# AQ_sensor_SIGFOX.net
KiCad netlist of a schematic drawn in EAGLE
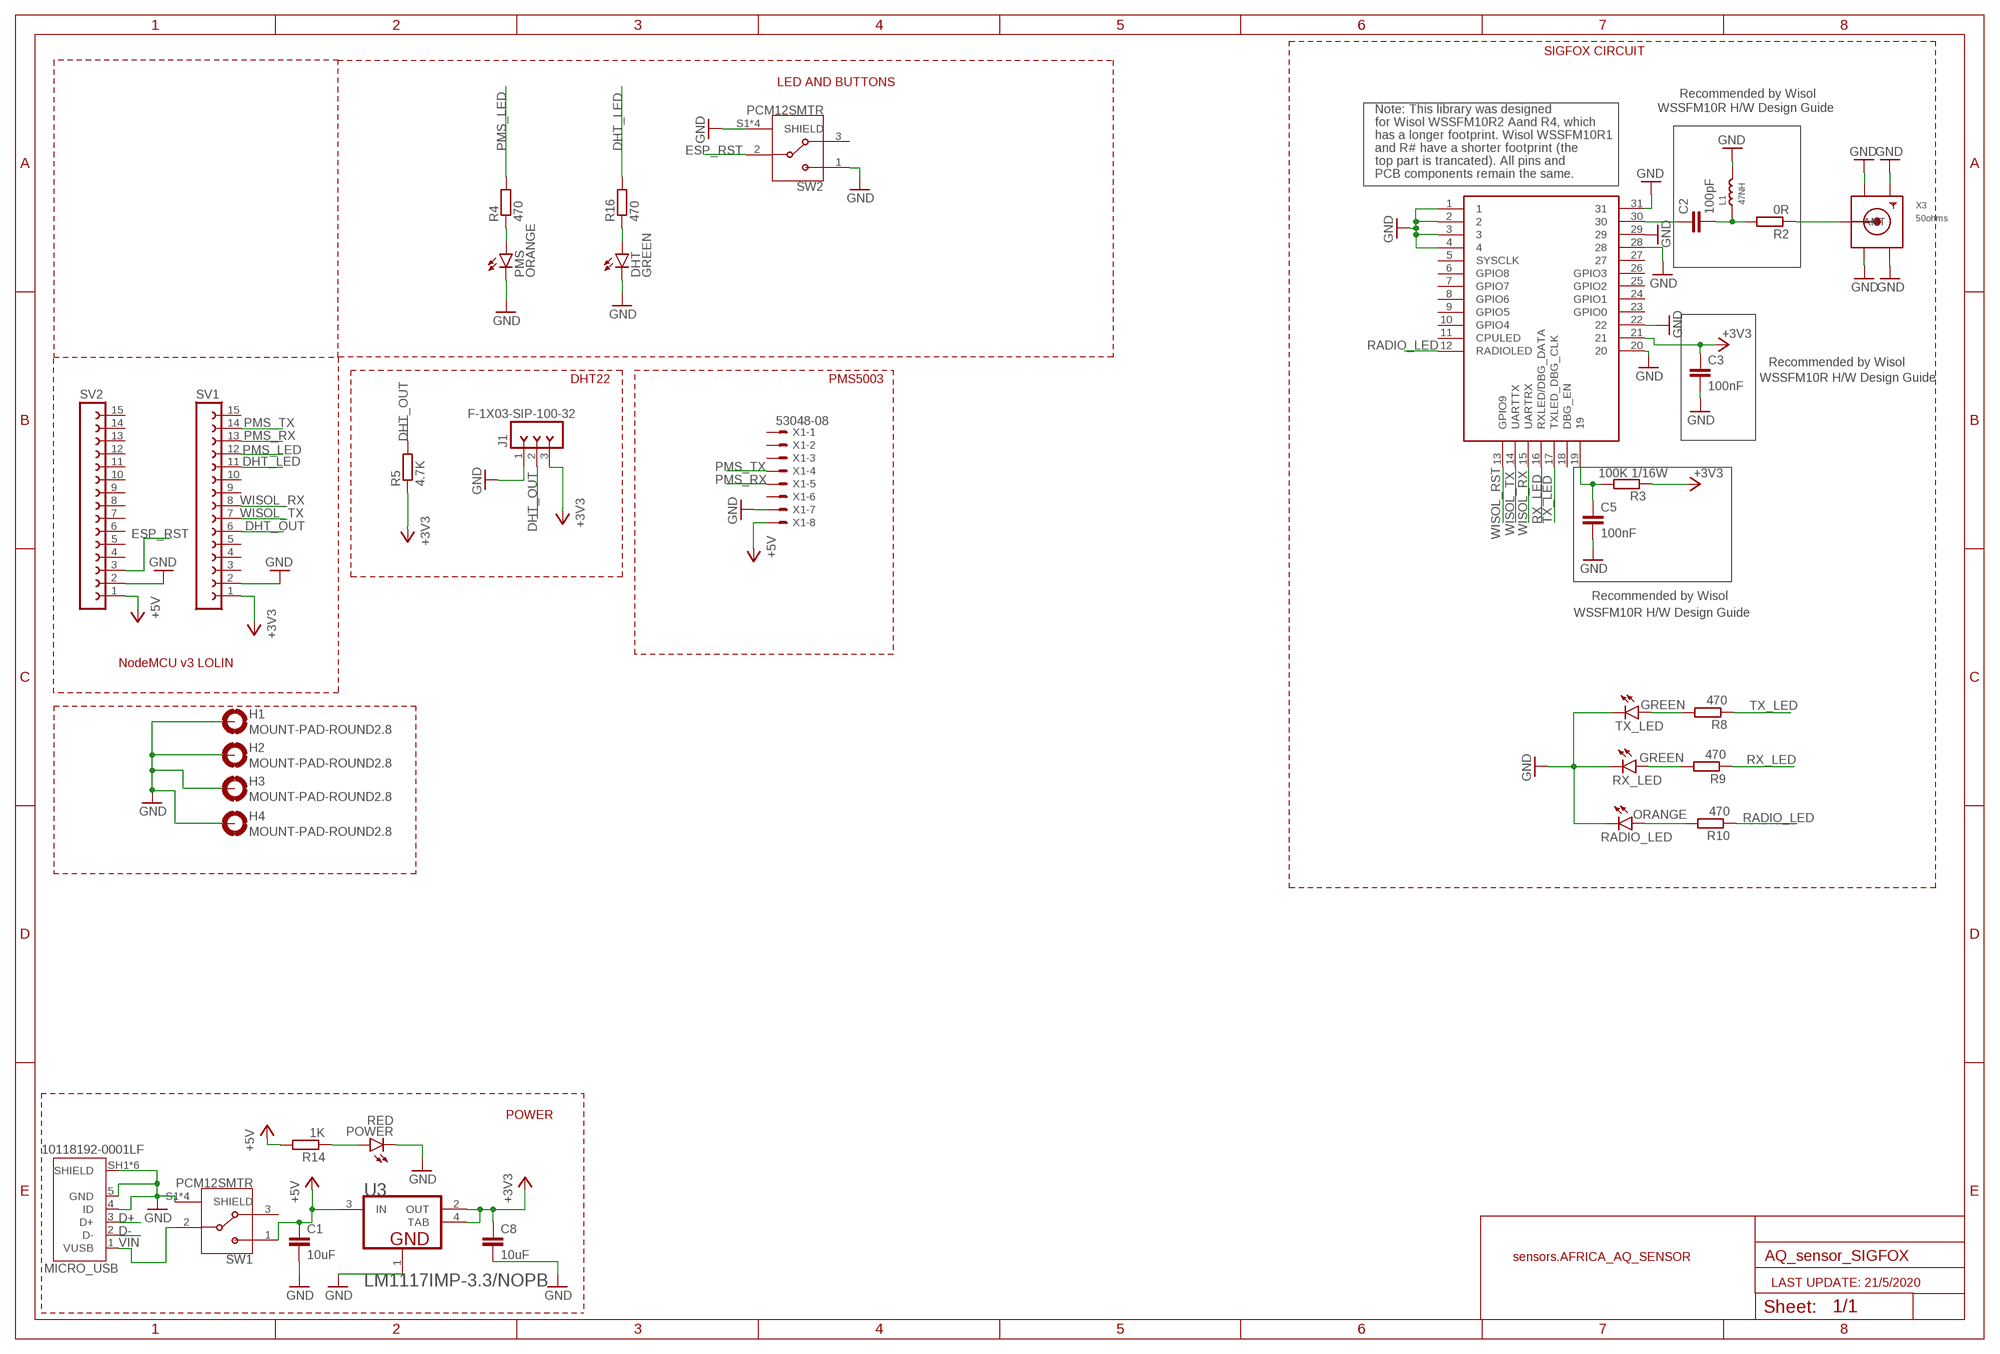
[diagram p0: schematic, sheet 1]

(export (version "E")
  (design (tool "Eeschema 10.0.6"))
  (components
    (comp (ref "C1")
      (value "10uF")
      (footprint "eagle-import:C0603")
      (libsource (lib "eagle-import") (part "C-EUC0603"))
    )
    (comp (ref "C2")
      (value "100pF")
      (footprint "eagle-import:C0603")
      (libsource (lib "eagle-import") (part "C-EUC0603"))
    )
    (comp (ref "C3")
      (value "100nF")
      (footprint "eagle-import:C0603")
      (libsource (lib "eagle-import") (part "C-EUC0603"))
    )
    (comp (ref "C5")
      (value "100nF")
      (footprint "eagle-import:C0603")
      (libsource (lib "eagle-import") (part "C-EUC0603"))
    )
    (comp (ref "C8")
      (value "10uF")
      (footprint "eagle-import:C0603")
      (libsource (lib "eagle-import") (part "C-EUC0603"))
    )
    (comp (ref "DHT")
      (value "GREEN")
      (footprint "eagle-import:CHIP-LED0603")
      (libsource (lib "eagle-import") (part "LEDCHIP-LED0603"))
    )
    (comp (ref "H1")
      (value "MOUNT-PAD-ROUND2.8")
      (footprint "eagle-import:2,8-PAD")
      (libsource (lib "eagle-import") (part "MOUNT-PAD-ROUND2.8"))
    )
    (comp (ref "H2")
      (value "MOUNT-PAD-ROUND2.8")
      (footprint "eagle-import:2,8-PAD")
      (libsource (lib "eagle-import") (part "MOUNT-PAD-ROUND2.8"))
    )
    (comp (ref "H3")
      (value "MOUNT-PAD-ROUND2.8")
      (footprint "eagle-import:2,8-PAD")
      (libsource (lib "eagle-import") (part "MOUNT-PAD-ROUND2.8"))
    )
    (comp (ref "H4")
      (value "MOUNT-PAD-ROUND2.8")
      (footprint "eagle-import:2,8-PAD")
      (libsource (lib "eagle-import") (part "MOUNT-PAD-ROUND2.8"))
    )
    (comp (ref "J1")
      (value "F-1X03-SIP-100-32")
      (footprint "eagle-import:SIP-100-03-32")
      (libsource (lib "eagle-import") (part "F-1X03-SIP-100-32"))
    )
    (comp (ref "L1")
      (value "47NH")
      (footprint "eagle-import:L0805")
      (fields (field (name "MPN") "LQM2MPN2R2MG0"))
      (libsource (lib "eagle-import") (part "SMD-INDUCTOR-2.2UH-20%-1.2A(0805)"))
    )
    (comp (ref "MICRO_USB")
      (value "10118192-0001LF")
      (footprint "eagle-import:AMPHENOL_10118192-0001LF")
      (fields (field (name "MF") "Amphenol ICC"))
      (libsource (lib "eagle-import") (part "10118192-0001LF"))
    )
    (comp (ref "PMS")
      (value "ORANGE")
      (footprint "eagle-import:CHIP-LED0603")
      (libsource (lib "eagle-import") (part "LEDCHIP-LED0603"))
    )
    (comp (ref "POWER")
      (value "RED")
      (footprint "eagle-import:CHIP-LED0603")
      (libsource (lib "eagle-import") (part "LEDCHIP-LED0603"))
    )
    (comp (ref "R2")
      (value "0R")
      (footprint "eagle-import:R0603")
      (libsource (lib "eagle-import") (part "R-EU_R0603"))
    )
    (comp (ref "R3")
      (value "100K 1/16W")
      (footprint "eagle-import:R0603")
      (libsource (lib "eagle-import") (part "R-EU_R0603"))
    )
    (comp (ref "R4")
      (value "470")
      (footprint "eagle-import:R0603")
      (libsource (lib "eagle-import") (part "R-EU_R0603"))
    )
    (comp (ref "R5")
      (value "4.7K")
      (footprint "eagle-import:R0603")
      (libsource (lib "eagle-import") (part "R-EU_R0603"))
    )
    (comp (ref "R8")
      (value "470")
      (footprint "eagle-import:R0603")
      (libsource (lib "eagle-import") (part "R-EU_R0603"))
    )
    (comp (ref "R9")
      (value "470")
      (footprint "eagle-import:R0603")
      (libsource (lib "eagle-import") (part "R-EU_R0603"))
    )
    (comp (ref "R10")
      (value "470")
      (footprint "eagle-import:R0603")
      (libsource (lib "eagle-import") (part "R-EU_R0603"))
    )
    (comp (ref "R14")
      (value "1K")
      (footprint "eagle-import:R0603")
      (libsource (lib "eagle-import") (part "R-EU_R0603"))
    )
    (comp (ref "R16")
      (value "470")
      (footprint "eagle-import:R0603")
      (libsource (lib "eagle-import") (part "R-EU_R0603"))
    )
    (comp (ref "RADIO_LED")
      (value "ORANGE")
      (footprint "eagle-import:CHIP-LED0603")
      (libsource (lib "eagle-import") (part "LEDCHIP-LED0603"))
    )
    (comp (ref "RX_LED")
      (value "GREEN")
      (footprint "eagle-import:CHIP-LED0603")
      (libsource (lib "eagle-import") (part "LEDCHIP-LED0603"))
    )
    (comp (ref "SV1")
      (value "FE15-1")
      (footprint "eagle-import:FE15")
      (libsource (lib "eagle-import") (part "FE15-1"))
    )
    (comp (ref "SV2")
      (value "FE15-1")
      (footprint "eagle-import:FE15")
      (libsource (lib "eagle-import") (part "FE15-1"))
    )
    (comp (ref "SW1")
      (value "PCM12SMTR")
      (footprint "eagle-import:SW_PCM12SMTR")
      (fields (field (name "MF") "C&K"))
      (libsource (lib "eagle-import") (part "PCM12SMTR"))
    )
    (comp (ref "SW2")
      (value "PCM12SMTR")
      (footprint "eagle-import:SW_PCM12SMTR")
      (fields (field (name "MF") "C&K"))
      (libsource (lib "eagle-import") (part "PCM12SMTR"))
    )
    (comp (ref "TX_LED")
      (value "GREEN")
      (footprint "eagle-import:CHIP-LED0603")
      (libsource (lib "eagle-import") (part "LEDCHIP-LED0603"))
    )
    (comp (ref "U$1")
      (value "WSSFM10RWSSFM10R2R4")
      (footprint "eagle-import:WSSFM10R")
      (libsource (lib "eagle-import") (part "WSSFM10RWSSFM10R2R4"))
    )
    (comp (ref "U3")
      (value "TEXAS_INSTRUMENTS_LM1117IMP-3.3-NOPBTEXAS_INSTRUMENTS_LM1117IMP-3.3-NOPB_0_0")
      (footprint "eagle-import:TEXAS_INSTRUMENTS_LM1117IMP-3.3-NOPB_0")
      (fields (field (name "MF") "Texas Instruments") (field (name "MPN") "LM1117IMP-3.3/NOPB"))
      (libsource (lib "eagle-import") (part "TEXAS_INSTRUMENTS_LM1117IMP-3.3-NOPBTEXAS_INSTRUMENTS_LM1117IMP-3.3-NOPB_0_0"))
    )
    (comp (ref "X1")
      (value "53048-08")
      (footprint "eagle-import:53048-08")
      (fields (field (name "MF") "WALDOM/MOLEX") (field (name "MPN") "53048-0810"))
      (libsource (lib "eagle-import") (part "53?-08048"))
    )
    (comp (ref "X3")
      (value "50ohms")
      (footprint "eagle-import:SMA_EDGELAUNCH_UFL")
      (libsource (lib "eagle-import") (part "SMACONNECTOR_EDGE_UFL"))
    )
  )
  (nets
    (net (code "1") (name "+3V3") (class "Default")
      (node (ref "C3") (pin "1") (pinfunction "1_1") (pintype "passive"))
      (node (ref "C8") (pin "1") (pinfunction "1_1") (pintype "passive"))
      (node (ref "J1") (pin "3") (pinfunction "3_3") (pintype "passive"))
      (node (ref "R3") (pin "1") (pinfunction "1_1") (pintype "passive"))
      (node (ref "R5") (pin "1") (pinfunction "1_1") (pintype "passive"))
      (node (ref "SV1") (pin "1") (pinfunction "1_1") (pintype "passive"))
      (node (ref "U$1") (pin "21") (pinfunction "21_21") (pintype "bidirectional"))
      (node (ref "U3") (pin "2") (pinfunction "OUT_2") (pintype "power_in"))
      (node (ref "U3") (pin "4") (pinfunction "TAB_4") (pintype "power_in"))
    )
    (net (code "2") (name "+5V") (class "Default")
      (node (ref "C1") (pin "1") (pinfunction "1_1") (pintype "passive"))
      (node (ref "R14") (pin "2") (pinfunction "2_2") (pintype "passive"))
      (node (ref "SV2") (pin "1") (pinfunction "1_1") (pintype "passive"))
      (node (ref "SW1") (pin "1") (pinfunction "1_1") (pintype "passive"))
      (node (ref "U3") (pin "3") (pinfunction "IN_3") (pintype "power_in"))
      (node (ref "X1") (pin "8") (pinfunction "S_8") (pintype "passive"))
    )
    (net (code "3") (name "/D+") (class "Default")
      (node (ref "MICRO_USB") (pin "3") (pinfunction "D+_3") (pintype "passive"))
    )
    (net (code "4") (name "/D-") (class "Default")
      (node (ref "MICRO_USB") (pin "2") (pinfunction "D-_2") (pintype "passive"))
    )
    (net (code "5") (name "/DHT_LED") (class "Default")
      (node (ref "R16") (pin "2") (pinfunction "2_2") (pintype "passive"))
      (node (ref "SV1") (pin "11") (pinfunction "11_11") (pintype "passive"))
    )
    (net (code "6") (name "/DHT_OUT") (class "Default")
      (node (ref "J1") (pin "2") (pinfunction "2_2") (pintype "passive"))
      (node (ref "R5") (pin "2") (pinfunction "2_2") (pintype "passive"))
      (node (ref "SV1") (pin "6") (pinfunction "6_6") (pintype "passive"))
    )
    (net (code "7") (name "/ESP_RST") (class "Default")
      (node (ref "SV2") (pin "3") (pinfunction "3_3") (pintype "passive"))
      (node (ref "SW2") (pin "2") (pinfunction "2_2") (pintype "passive"))
    )
    (net (code "8") (name "/PMS_LED") (class "Default")
      (node (ref "R4") (pin "2") (pinfunction "2_2") (pintype "passive"))
      (node (ref "SV1") (pin "12") (pinfunction "12_12") (pintype "passive"))
    )
    (net (code "9") (name "/PMS_RX") (class "Default")
      (node (ref "SV1") (pin "13") (pinfunction "13_13") (pintype "passive"))
      (node (ref "X1") (pin "5") (pinfunction "S_5") (pintype "passive"))
    )
    (net (code "10") (name "/PMS_TX") (class "Default")
      (node (ref "SV1") (pin "14") (pinfunction "14_14") (pintype "passive"))
      (node (ref "X1") (pin "4") (pinfunction "S_4") (pintype "passive"))
    )
    (net (code "11") (name "/RADIO_LED") (class "Default")
      (node (ref "R10") (pin "1") (pinfunction "1_1") (pintype "passive"))
      (node (ref "U$1") (pin "12") (pinfunction "RADIOLED_12") (pintype "bidirectional"))
    )
    (net (code "12") (name "/RX_LED") (class "Default")
      (node (ref "R9") (pin "1") (pinfunction "1_1") (pintype "passive"))
      (node (ref "U$1") (pin "16") (pinfunction "RXLED/DBG_DATA_16") (pintype "bidirectional"))
    )
    (net (code "13") (name "/TX_LED") (class "Default")
      (node (ref "R8") (pin "1") (pinfunction "1_1") (pintype "passive"))
      (node (ref "U$1") (pin "17") (pinfunction "TXLED_DBG_CLK_17") (pintype "bidirectional"))
    )
    (net (code "14") (name "/VIN") (class "Default")
      (node (ref "MICRO_USB") (pin "1") (pinfunction "VUSB_1") (pintype "passive"))
      (node (ref "SW1") (pin "2") (pinfunction "2_2") (pintype "passive"))
    )
    (net (code "15") (name "/WISOL_RST") (class "Default")
      (node (ref "U$1") (pin "13") (pinfunction "GPIO9_13") (pintype "bidirectional"))
    )
    (net (code "16") (name "/WISOL_RX") (class "Default")
      (node (ref "SV1") (pin "8") (pinfunction "8_8") (pintype "passive"))
      (node (ref "U$1") (pin "15") (pinfunction "UARTRX_15") (pintype "bidirectional"))
    )
    (net (code "17") (name "/WISOL_TX") (class "Default")
      (node (ref "SV1") (pin "7") (pinfunction "7_7") (pintype "passive"))
      (node (ref "U$1") (pin "14") (pinfunction "UARTTX_14") (pintype "bidirectional"))
    )
    (net (code "18") (name "GND") (class "Default")
      (node (ref "C1") (pin "2") (pinfunction "2_2") (pintype "passive"))
      (node (ref "C3") (pin "2") (pinfunction "2_2") (pintype "passive"))
      (node (ref "C5") (pin "2") (pinfunction "2_2") (pintype "passive"))
      (node (ref "C8") (pin "2") (pinfunction "2_2") (pintype "passive"))
      (node (ref "DHT") (pin "C") (pinfunction "C_C") (pintype "passive"))
      (node (ref "H1") (pin "B2,8") (pinfunction "MOUNT_B2,8") (pintype "passive"))
      (node (ref "H2") (pin "B2,8") (pinfunction "MOUNT_B2,8") (pintype "passive"))
      (node (ref "H3") (pin "B2,8") (pinfunction "MOUNT_B2,8") (pintype "passive"))
      (node (ref "H4") (pin "B2,8") (pinfunction "MOUNT_B2,8") (pintype "passive"))
      (node (ref "J1") (pin "1") (pinfunction "1_1") (pintype "passive"))
      (node (ref "L1") (pin "2") (pinfunction "2_2") (pintype "passive"))
      (node (ref "MICRO_USB") (pin "4") (pinfunction "ID_4") (pintype "passive"))
      (node (ref "MICRO_USB") (pin "5") (pinfunction "GND_5") (pintype "passive"))
      (node (ref "MICRO_USB") (pin "SH1") (pinfunction "SHIELD_SH1") (pintype "passive"))
      (node (ref "MICRO_USB") (pin "SH2") (pinfunction "SHIELD_SH2") (pintype "passive"))
      (node (ref "MICRO_USB") (pin "SH3") (pinfunction "SHIELD_SH3") (pintype "passive"))
      (node (ref "MICRO_USB") (pin "SH4") (pinfunction "SHIELD_SH4") (pintype "passive"))
      (node (ref "MICRO_USB") (pin "SH5") (pinfunction "SHIELD_SH5") (pintype "passive"))
      (node (ref "MICRO_USB") (pin "SH6") (pinfunction "SHIELD_SH6") (pintype "passive"))
      (node (ref "PMS") (pin "C") (pinfunction "C_C") (pintype "passive"))
      (node (ref "POWER") (pin "C") (pinfunction "C_C") (pintype "passive"))
      (node (ref "RADIO_LED") (pin "C") (pinfunction "C_C") (pintype "passive"))
      (node (ref "RX_LED") (pin "C") (pinfunction "C_C") (pintype "passive"))
      (node (ref "SV1") (pin "2") (pinfunction "2_2") (pintype "passive"))
      (node (ref "SV2") (pin "2") (pinfunction "2_2") (pintype "passive"))
      (node (ref "SW1") (pin "S1") (pinfunction "SHIELD_S1") (pintype "passive"))
      (node (ref "SW1") (pin "S2") (pinfunction "SHIELD_S2") (pintype "passive"))
      (node (ref "SW1") (pin "S3") (pinfunction "SHIELD_S3") (pintype "passive"))
      (node (ref "SW1") (pin "S4") (pinfunction "SHIELD_S4") (pintype "passive"))
      (node (ref "SW2") (pin "1") (pinfunction "1_1") (pintype "passive"))
      (node (ref "SW2") (pin "S1") (pinfunction "SHIELD_S1") (pintype "passive"))
      (node (ref "SW2") (pin "S2") (pinfunction "SHIELD_S2") (pintype "passive"))
      (node (ref "SW2") (pin "S3") (pinfunction "SHIELD_S3") (pintype "passive"))
      (node (ref "SW2") (pin "S4") (pinfunction "SHIELD_S4") (pintype "passive"))
      (node (ref "TX_LED") (pin "C") (pinfunction "C_C") (pintype "passive"))
      (node (ref "U$1") (pin "1") (pinfunction "1_1") (pintype "bidirectional"))
      (node (ref "U$1") (pin "2") (pinfunction "2_2") (pintype "bidirectional"))
      (node (ref "U$1") (pin "20") (pinfunction "20_20") (pintype "bidirectional"))
      (node (ref "U$1") (pin "22") (pinfunction "22_22") (pintype "bidirectional"))
      (node (ref "U$1") (pin "28") (pinfunction "28_28") (pintype "bidirectional"))
      (node (ref "U$1") (pin "29") (pinfunction "29_29") (pintype "bidirectional"))
      (node (ref "U$1") (pin "3") (pinfunction "3_3") (pintype "bidirectional"))
      (node (ref "U$1") (pin "31") (pinfunction "31_31") (pintype "bidirectional"))
      (node (ref "U$1") (pin "4") (pinfunction "4_4") (pintype "bidirectional"))
      (node (ref "U3") (pin "1") (pinfunction "GND_1") (pintype "power_in"))
      (node (ref "X1") (pin "7") (pinfunction "S_7") (pintype "passive"))
      (node (ref "X3") (pin "GND@1") (pinfunction "GND1_GND@1") (pintype "power_in"))
      (node (ref "X3") (pin "GND@2") (pinfunction "GND2_GND@2") (pintype "power_in"))
      (node (ref "X3") (pin "GND@3") (pinfunction "GND3_GND@3") (pintype "power_in"))
      (node (ref "X3") (pin "GND@4") (pinfunction "GND4_GND@4") (pintype "power_in"))
    )
    (net (code "19") (name "Net-(C2-Pad1)") (class "Default")
      (node (ref "C2") (pin "1") (pinfunction "1_1") (pintype "passive"))
      (node (ref "U$1") (pin "30") (pinfunction "30_30") (pintype "bidirectional"))
    )
    (net (code "20") (name "Net-(C2-Pad2)") (class "Default")
      (node (ref "C2") (pin "2") (pinfunction "2_2") (pintype "passive"))
      (node (ref "L1") (pin "1") (pinfunction "1_1") (pintype "passive"))
      (node (ref "R2") (pin "2") (pinfunction "2_2") (pintype "passive"))
    )
    (net (code "21") (name "Net-(C5-Pad1)") (class "Default")
      (node (ref "C5") (pin "1") (pinfunction "1_1") (pintype "passive"))
      (node (ref "R3") (pin "2") (pinfunction "2_2") (pintype "passive"))
      (node (ref "U$1") (pin "19") (pinfunction "19_19") (pintype "bidirectional"))
    )
    (net (code "22") (name "Net-(DHT-PadA)") (class "Default")
      (node (ref "DHT") (pin "A") (pinfunction "A_A") (pintype "passive"))
      (node (ref "R16") (pin "1") (pinfunction "1_1") (pintype "passive"))
    )
    (net (code "23") (name "Net-(PMS-PadA)") (class "Default")
      (node (ref "PMS") (pin "A") (pinfunction "A_A") (pintype "passive"))
      (node (ref "R4") (pin "1") (pinfunction "1_1") (pintype "passive"))
    )
    (net (code "24") (name "Net-(POWER-PadA)") (class "Default")
      (node (ref "POWER") (pin "A") (pinfunction "A_A") (pintype "passive"))
      (node (ref "R14") (pin "1") (pinfunction "1_1") (pintype "passive"))
    )
    (net (code "25") (name "Net-(R8-Pad2)") (class "Default")
      (node (ref "R8") (pin "2") (pinfunction "2_2") (pintype "passive"))
      (node (ref "TX_LED") (pin "A") (pinfunction "A_A") (pintype "passive"))
    )
    (net (code "26") (name "Net-(R9-Pad2)") (class "Default")
      (node (ref "R9") (pin "2") (pinfunction "2_2") (pintype "passive"))
      (node (ref "RX_LED") (pin "A") (pinfunction "A_A") (pintype "passive"))
    )
    (net (code "27") (name "Net-(R10-Pad2)") (class "Default")
      (node (ref "R10") (pin "2") (pinfunction "2_2") (pintype "passive"))
      (node (ref "RADIO_LED") (pin "A") (pinfunction "A_A") (pintype "passive"))
    )
    (net (code "28") (name "Net-(X3-ANT)") (class "Default")
      (node (ref "R2") (pin "1") (pinfunction "1_1") (pintype "passive"))
      (node (ref "X3") (pin "P") (pinfunction "ANT_P") (pintype "bidirectional"))
    )
    (net (code "29") (name "unconnected-(SV1-Pad3)") (class "Default")
      (node (ref "SV1") (pin "3") (pinfunction "3_3") (pintype "passive"))
    )
    (net (code "30") (name "unconnected-(SV1-Pad4)") (class "Default")
      (node (ref "SV1") (pin "4") (pinfunction "4_4") (pintype "passive"))
    )
    (net (code "31") (name "unconnected-(SV1-Pad5)") (class "Default")
      (node (ref "SV1") (pin "5") (pinfunction "5_5") (pintype "passive"))
    )
    (net (code "32") (name "unconnected-(SV1-Pad9)") (class "Default")
      (node (ref "SV1") (pin "9") (pinfunction "9_9") (pintype "passive"))
    )
    (net (code "33") (name "unconnected-(SV1-Pad10)") (class "Default")
      (node (ref "SV1") (pin "10") (pinfunction "10_10") (pintype "passive"))
    )
    (net (code "34") (name "unconnected-(SV1-Pad15)") (class "Default")
      (node (ref "SV1") (pin "15") (pinfunction "15_15") (pintype "passive"))
    )
    (net (code "35") (name "unconnected-(SV2-Pad4)") (class "Default")
      (node (ref "SV2") (pin "4") (pinfunction "4_4") (pintype "passive"))
    )
    (net (code "36") (name "unconnected-(SV2-Pad5)") (class "Default")
      (node (ref "SV2") (pin "5") (pinfunction "5_5") (pintype "passive"))
    )
    (net (code "37") (name "unconnected-(SV2-Pad6)") (class "Default")
      (node (ref "SV2") (pin "6") (pinfunction "6_6") (pintype "passive"))
    )
    (net (code "38") (name "unconnected-(SV2-Pad7)") (class "Default")
      (node (ref "SV2") (pin "7") (pinfunction "7_7") (pintype "passive"))
    )
    (net (code "39") (name "unconnected-(SV2-Pad8)") (class "Default")
      (node (ref "SV2") (pin "8") (pinfunction "8_8") (pintype "passive"))
    )
    (net (code "40") (name "unconnected-(SV2-Pad9)") (class "Default")
      (node (ref "SV2") (pin "9") (pinfunction "9_9") (pintype "passive"))
    )
    (net (code "41") (name "unconnected-(SV2-Pad10)") (class "Default")
      (node (ref "SV2") (pin "10") (pinfunction "10_10") (pintype "passive"))
    )
    (net (code "42") (name "unconnected-(SV2-Pad11)") (class "Default")
      (node (ref "SV2") (pin "11") (pinfunction "11_11") (pintype "passive"))
    )
    (net (code "43") (name "unconnected-(SV2-Pad12)") (class "Default")
      (node (ref "SV2") (pin "12") (pinfunction "12_12") (pintype "passive"))
    )
    (net (code "44") (name "unconnected-(SV2-Pad13)") (class "Default")
      (node (ref "SV2") (pin "13") (pinfunction "13_13") (pintype "passive"))
    )
    (net (code "45") (name "unconnected-(SV2-Pad14)") (class "Default")
      (node (ref "SV2") (pin "14") (pinfunction "14_14") (pintype "passive"))
    )
    (net (code "46") (name "unconnected-(SV2-Pad15)") (class "Default")
      (node (ref "SV2") (pin "15") (pinfunction "15_15") (pintype "passive"))
    )
    (net (code "47") (name "unconnected-(SW1-Pad3)") (class "Default")
      (node (ref "SW1") (pin "3") (pinfunction "3_3") (pintype "passive"))
    )
    (net (code "48") (name "unconnected-(SW2-Pad3)") (class "Default")
      (node (ref "SW2") (pin "3") (pinfunction "3_3") (pintype "passive"))
    )
    (net (code "49") (name "unconnected-(U$1-CPULED-Pad11)") (class "Default")
      (node (ref "U$1") (pin "11") (pinfunction "CPULED_11") (pintype "bidirectional"))
    )
    (net (code "50") (name "unconnected-(U$1-DBG_EN-Pad18)") (class "Default")
      (node (ref "U$1") (pin "18") (pinfunction "DBG_EN_18") (pintype "bidirectional"))
    )
    (net (code "51") (name "unconnected-(U$1-GPIO0-Pad23)") (class "Default")
      (node (ref "U$1") (pin "23") (pinfunction "GPIO0_23") (pintype "bidirectional"))
    )
    (net (code "52") (name "unconnected-(U$1-GPIO1-Pad24)") (class "Default")
      (node (ref "U$1") (pin "24") (pinfunction "GPIO1_24") (pintype "bidirectional"))
    )
    (net (code "53") (name "unconnected-(U$1-GPIO2-Pad25)") (class "Default")
      (node (ref "U$1") (pin "25") (pinfunction "GPIO2_25") (pintype "bidirectional"))
    )
    (net (code "54") (name "unconnected-(U$1-GPIO3-Pad26)") (class "Default")
      (node (ref "U$1") (pin "26") (pinfunction "GPIO3_26") (pintype "bidirectional"))
    )
    (net (code "55") (name "unconnected-(U$1-GPIO4-Pad10)") (class "Default")
      (node (ref "U$1") (pin "10") (pinfunction "GPIO4_10") (pintype "bidirectional"))
    )
    (net (code "56") (name "unconnected-(U$1-GPIO5-Pad9)") (class "Default")
      (node (ref "U$1") (pin "9") (pinfunction "GPIO5_9") (pintype "bidirectional"))
    )
    (net (code "57") (name "unconnected-(U$1-GPIO6-Pad8)") (class "Default")
      (node (ref "U$1") (pin "8") (pinfunction "GPIO6_8") (pintype "bidirectional"))
    )
    (net (code "58") (name "unconnected-(U$1-GPIO7-Pad7)") (class "Default")
      (node (ref "U$1") (pin "7") (pinfunction "GPIO7_7") (pintype "bidirectional"))
    )
    (net (code "59") (name "unconnected-(U$1-GPIO8-Pad6)") (class "Default")
      (node (ref "U$1") (pin "6") (pinfunction "GPIO8_6") (pintype "bidirectional"))
    )
    (net (code "60") (name "unconnected-(U$1-Pad27)") (class "Default")
      (node (ref "U$1") (pin "27") (pinfunction "27_27") (pintype "bidirectional"))
    )
    (net (code "61") (name "unconnected-(U$1-SYSCLK-Pad5)") (class "Default")
      (node (ref "U$1") (pin "5") (pinfunction "SYSCLK_5") (pintype "bidirectional"))
    )
    (net (code "62") (name "unconnected-(X1A-S-Pad1)") (class "Default")
      (node (ref "X1") (pin "1") (pinfunction "S_1") (pintype "passive"))
    )
    (net (code "63") (name "unconnected-(X1B-S-Pad2)") (class "Default")
      (node (ref "X1") (pin "2") (pinfunction "S_2") (pintype "passive"))
    )
    (net (code "64") (name "unconnected-(X1C-S-Pad3)") (class "Default")
      (node (ref "X1") (pin "3") (pinfunction "S_3") (pintype "passive"))
    )
    (net (code "65") (name "unconnected-(X1F-S-Pad6)") (class "Default")
      (node (ref "X1") (pin "6") (pinfunction "S_6") (pintype "passive"))
    )
  )
)
